# LCD_KEYb_final_rev02.net
KiCad netlist of a schematic drawn in EAGLE
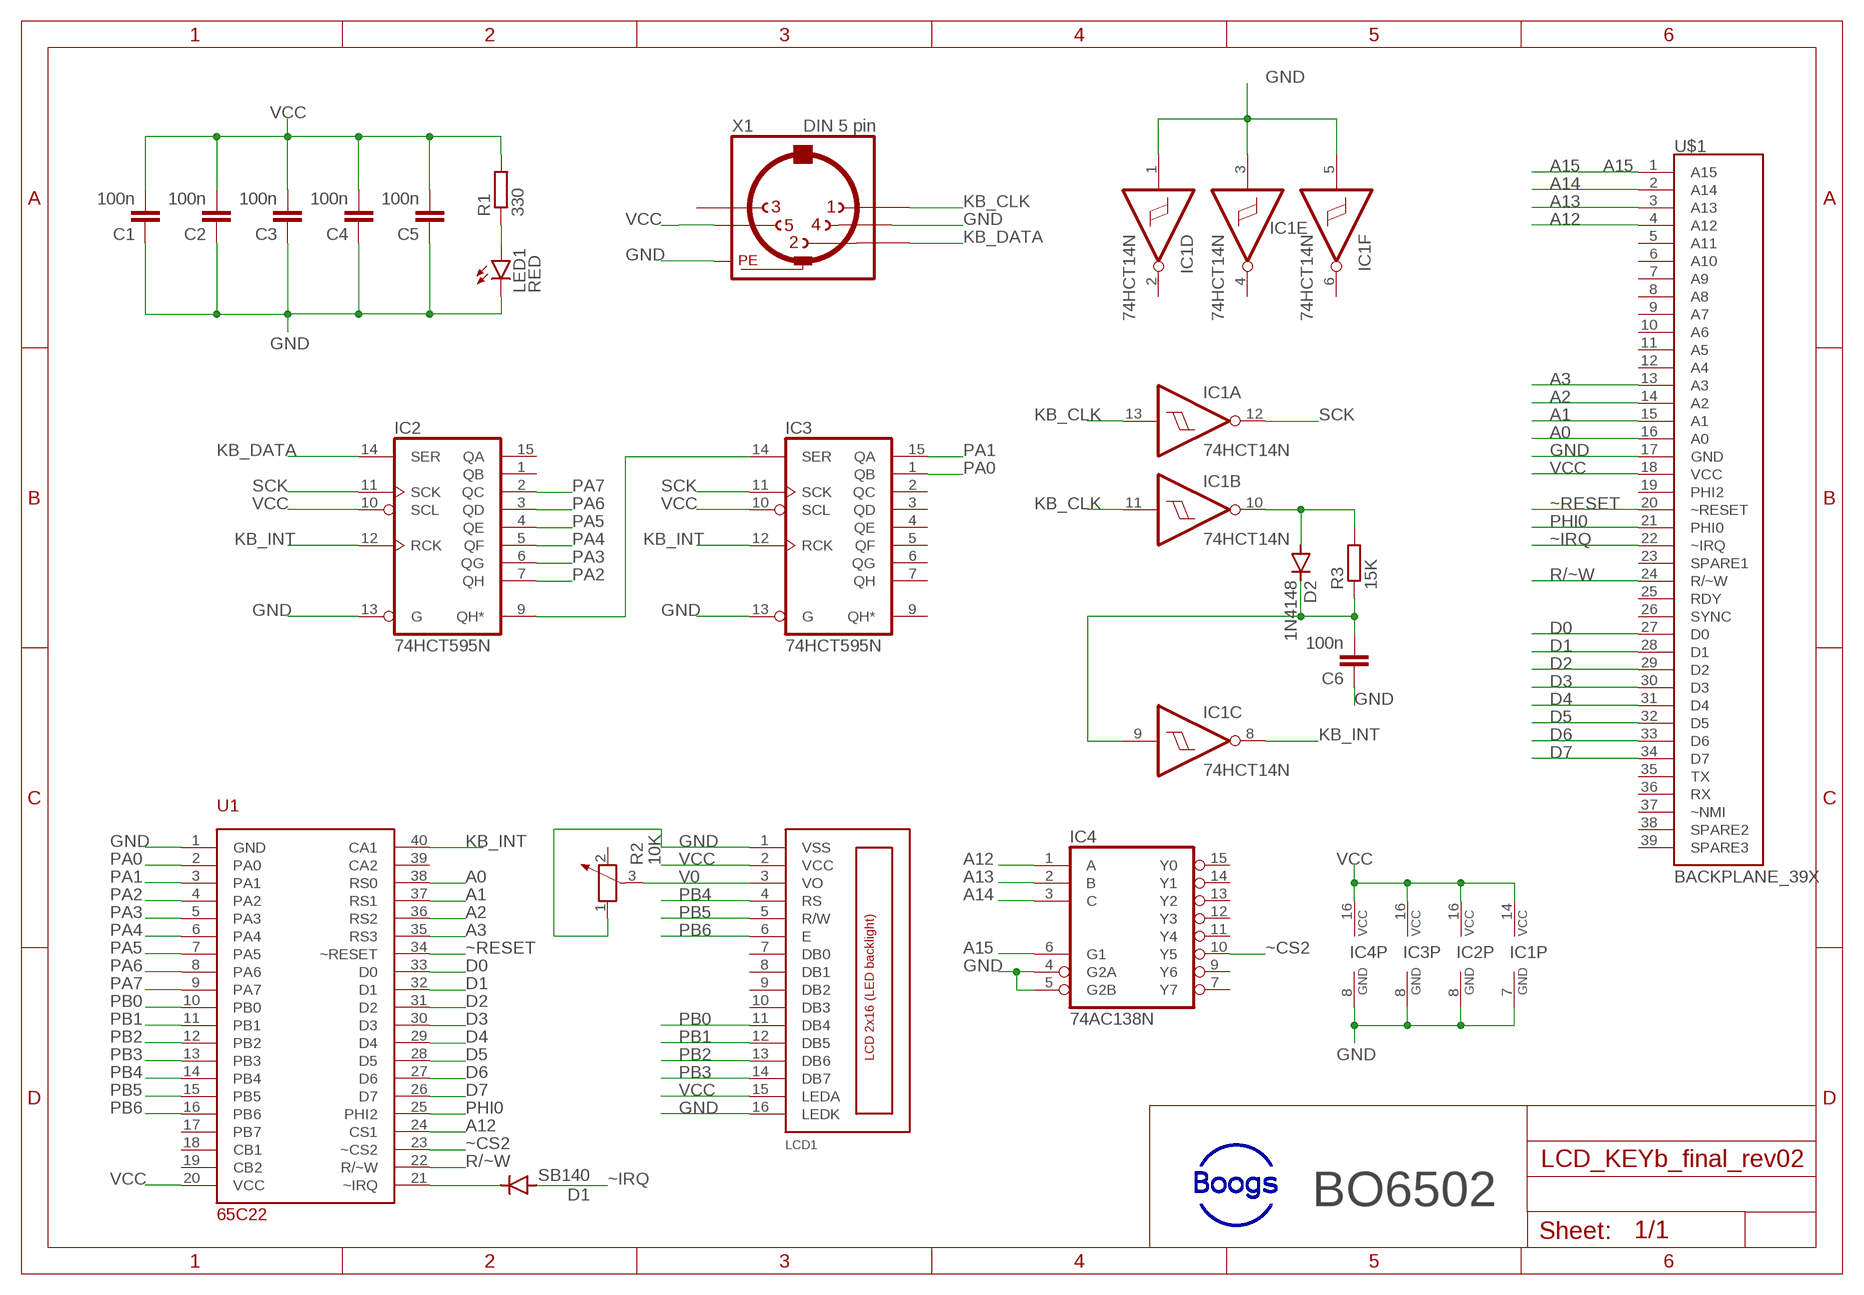
[diagram p0: schematic, sheet 1]

(export (version "E")
  (design (tool "Eeschema 10.0.6"))
  (components
    (comp (ref "C1")
      (value "100n")
      (footprint "eagle-import:C025-025X050")
      (libsource (lib "eagle-import") (part "C-EU025-025X050"))
    )
    (comp (ref "C2")
      (value "100n")
      (footprint "eagle-import:C025-025X050")
      (libsource (lib "eagle-import") (part "C-EU025-025X050"))
    )
    (comp (ref "C3")
      (value "100n")
      (footprint "eagle-import:C025-025X050")
      (libsource (lib "eagle-import") (part "C-EU025-025X050"))
    )
    (comp (ref "C4")
      (value "100n")
      (footprint "eagle-import:C025-025X050")
      (libsource (lib "eagle-import") (part "C-EU025-025X050"))
    )
    (comp (ref "C5")
      (value "100n")
      (footprint "eagle-import:C025-025X050")
      (libsource (lib "eagle-import") (part "C-EU025-025X050"))
    )
    (comp (ref "C6")
      (value "100n")
      (footprint "eagle-import:C025-025X050")
      (libsource (lib "eagle-import") (part "C-EU025-025X050"))
    )
    (comp (ref "D1")
      (value "SB140")
      (footprint "eagle-import:DO41-10")
      (libsource (lib "eagle-import") (part "1N4004"))
    )
    (comp (ref "D2")
      (value "1N4148")
      (footprint "eagle-import:DO35-7")
      (libsource (lib "eagle-import") (part "1N4148DO35-7"))
    )
    (comp (ref "IC1")
      (value "74HCT14N")
      (footprint "eagle-import:DIL14")
      (libsource (lib "eagle-import") (part "7414NHCT"))
    )
    (comp (ref "IC2")
      (value "74HCT595N")
      (footprint "eagle-import:DIL16")
      (libsource (lib "eagle-import") (part "74595NHCT"))
    )
    (comp (ref "IC3")
      (value "74HCT595N")
      (footprint "eagle-import:DIL16")
      (libsource (lib "eagle-import") (part "74595NHCT"))
    )
    (comp (ref "IC4")
      (value "74AC138N")
      (footprint "eagle-import:DIL16")
      (libsource (lib "eagle-import") (part "74138NAC"))
    )
    (comp (ref "LCD1")
      (value "LCD_2X16_SIL")
      (footprint "eagle-import:HY-1602F")
      (libsource (lib "eagle-import") (part "LCD_2X16_SIL"))
    )
    (comp (ref "LED1")
      (value "RED")
      (footprint "eagle-import:LED5MM")
      (libsource (lib "eagle-import") (part "LED5MM"))
    )
    (comp (ref "R1")
      (value "330")
      (footprint "eagle-import:0207_10")
      (libsource (lib "eagle-import") (part "R-EU_0207/10"))
    )
    (comp (ref "R2")
      (value "10K")
      (footprint "eagle-import:PT-10")
      (libsource (lib "eagle-import") (part "POTENTIOMETER_PT-10"))
    )
    (comp (ref "R3")
      (value "15K")
      (footprint "eagle-import:0207_10")
      (libsource (lib "eagle-import") (part "R-EU_0207/10"))
    )
    (comp (ref "U$1")
      (value "BACKPLANE_39X")
      (footprint "eagle-import:BP_39X")
      (fields (field (name "A15") "A15"))
      (libsource (lib "eagle-import") (part "BACKPLANE_39X"))
    )
    (comp (ref "U1")
      (value "65C22")
      (footprint "eagle-import:DIL40")
      (libsource (lib "eagle-import") (part "65C22"))
    )
    (comp (ref "X1")
      (value "DIN 5 pin")
      (footprint "eagle-import:MAB5SH")
      (libsource (lib "eagle-import") (part "MAB5SH"))
    )
  )
  (nets
    (net (code "1") (name "/A0") (class "Default")
      (node (ref "U$1") (pin "16") (pinfunction "A0_16") (pintype "bidirectional"))
      (node (ref "U1") (pin "38") (pinfunction "RS0_38") (pintype "bidirectional"))
    )
    (net (code "2") (name "/A1") (class "Default")
      (node (ref "U$1") (pin "15") (pinfunction "A1_15") (pintype "bidirectional"))
      (node (ref "U1") (pin "37") (pinfunction "RS1_37") (pintype "bidirectional"))
    )
    (net (code "3") (name "/A2") (class "Default")
      (node (ref "U$1") (pin "14") (pinfunction "A2_14") (pintype "bidirectional"))
      (node (ref "U1") (pin "36") (pinfunction "RS2_36") (pintype "bidirectional"))
    )
    (net (code "4") (name "/A3") (class "Default")
      (node (ref "U$1") (pin "13") (pinfunction "A3_13") (pintype "bidirectional"))
      (node (ref "U1") (pin "35") (pinfunction "RS3_35") (pintype "bidirectional"))
    )
    (net (code "5") (name "/A12") (class "Default")
      (node (ref "IC4") (pin "1") (pinfunction "A_1") (pintype "input"))
      (node (ref "U$1") (pin "4") (pinfunction "A12_4") (pintype "bidirectional"))
      (node (ref "U1") (pin "24") (pinfunction "CS1_24") (pintype "bidirectional"))
    )
    (net (code "6") (name "/A13") (class "Default")
      (node (ref "IC4") (pin "2") (pinfunction "B_2") (pintype "input"))
      (node (ref "U$1") (pin "3") (pinfunction "A13_3") (pintype "bidirectional"))
    )
    (net (code "7") (name "/A14") (class "Default")
      (node (ref "IC4") (pin "3") (pinfunction "C_3") (pintype "input"))
      (node (ref "U$1") (pin "2") (pinfunction "A14_2") (pintype "bidirectional"))
    )
    (net (code "8") (name "/A15") (class "Default")
      (node (ref "IC4") (pin "6") (pinfunction "G1_6") (pintype "input"))
      (node (ref "U$1") (pin "1") (pinfunction "A15_1") (pintype "bidirectional"))
    )
    (net (code "9") (name "/D0") (class "Default")
      (node (ref "U$1") (pin "27") (pinfunction "D0_27") (pintype "bidirectional"))
      (node (ref "U1") (pin "33") (pinfunction "D0_33") (pintype "bidirectional"))
    )
    (net (code "10") (name "/D1") (class "Default")
      (node (ref "U$1") (pin "28") (pinfunction "D1_28") (pintype "bidirectional"))
      (node (ref "U1") (pin "32") (pinfunction "D1_32") (pintype "bidirectional"))
    )
    (net (code "11") (name "/D2") (class "Default")
      (node (ref "U$1") (pin "29") (pinfunction "D2_29") (pintype "bidirectional"))
      (node (ref "U1") (pin "31") (pinfunction "D2_31") (pintype "bidirectional"))
    )
    (net (code "12") (name "/D3") (class "Default")
      (node (ref "U$1") (pin "30") (pinfunction "D3_30") (pintype "bidirectional"))
      (node (ref "U1") (pin "30") (pinfunction "D3_30") (pintype "bidirectional"))
    )
    (net (code "13") (name "/D4") (class "Default")
      (node (ref "U$1") (pin "31") (pinfunction "D4_31") (pintype "bidirectional"))
      (node (ref "U1") (pin "29") (pinfunction "D4_29") (pintype "bidirectional"))
    )
    (net (code "14") (name "/D5") (class "Default")
      (node (ref "U$1") (pin "32") (pinfunction "D5_32") (pintype "bidirectional"))
      (node (ref "U1") (pin "28") (pinfunction "D5_28") (pintype "bidirectional"))
    )
    (net (code "15") (name "/D6") (class "Default")
      (node (ref "U$1") (pin "33") (pinfunction "D6_33") (pintype "bidirectional"))
      (node (ref "U1") (pin "27") (pinfunction "D6_27") (pintype "bidirectional"))
    )
    (net (code "16") (name "/D7") (class "Default")
      (node (ref "U$1") (pin "34") (pinfunction "D7_34") (pintype "bidirectional"))
      (node (ref "U1") (pin "26") (pinfunction "D7_26") (pintype "bidirectional"))
    )
    (net (code "17") (name "/GND") (class "Default")
      (node (ref "C1") (pin "1") (pinfunction "1_1") (pintype "passive"))
      (node (ref "C2") (pin "1") (pinfunction "1_1") (pintype "passive"))
      (node (ref "C3") (pin "1") (pinfunction "1_1") (pintype "passive"))
      (node (ref "C4") (pin "1") (pinfunction "1_1") (pintype "passive"))
      (node (ref "C5") (pin "1") (pinfunction "1_1") (pintype "passive"))
      (node (ref "C6") (pin "1") (pinfunction "1_1") (pintype "passive"))
      (node (ref "IC1") (pin "1") (pinfunction "I_1") (pintype "input"))
      (node (ref "IC1") (pin "3") (pinfunction "I_3") (pintype "input"))
      (node (ref "IC1") (pin "5") (pinfunction "I_5") (pintype "input"))
      (node (ref "IC1") (pin "7") (pinfunction "GND_7") (pintype "power_in"))
      (node (ref "IC2") (pin "13") (pinfunction "G_13") (pintype "input"))
      (node (ref "IC2") (pin "8") (pinfunction "GND_8") (pintype "power_in"))
      (node (ref "IC3") (pin "13") (pinfunction "G_13") (pintype "input"))
      (node (ref "IC3") (pin "8") (pinfunction "GND_8") (pintype "power_in"))
      (node (ref "IC4") (pin "4") (pinfunction "G2A_4") (pintype "input"))
      (node (ref "IC4") (pin "5") (pinfunction "G2B_5") (pintype "input"))
      (node (ref "IC4") (pin "8") (pinfunction "GND_8") (pintype "power_in"))
      (node (ref "LCD1") (pin "1") (pinfunction "VSS_1") (pintype "power_in"))
      (node (ref "LCD1") (pin "16") (pinfunction "LEDK_16") (pintype "passive"))
      (node (ref "LED1") (pin "K") (pinfunction "C_K") (pintype "passive"))
      (node (ref "R2") (pin "1") (pinfunction "1_1") (pintype "passive"))
      (node (ref "U$1") (pin "17") (pinfunction "GND_17") (pintype "bidirectional"))
      (node (ref "U1") (pin "1") (pinfunction "GND_1") (pintype "bidirectional"))
      (node (ref "X1") (pin "4") (pinfunction "4_4") (pintype "passive"))
      (node (ref "X1") (pin "PE") (pinfunction "PE_PE") (pintype "power_in"))
      (node (ref "X1") (pin "PE@") (pinfunction "PE_PE@") (pintype "power_in"))
    )
    (net (code "18") (name "/KB_CLK") (class "Default")
      (node (ref "IC1") (pin "11") (pinfunction "I_11") (pintype "input"))
      (node (ref "IC1") (pin "13") (pinfunction "I_13") (pintype "input"))
      (node (ref "X1") (pin "1") (pinfunction "1_1") (pintype "passive"))
    )
    (net (code "19") (name "/KB_DATA") (class "Default")
      (node (ref "IC2") (pin "14") (pinfunction "SER_14") (pintype "input"))
      (node (ref "X1") (pin "2") (pinfunction "2_2") (pintype "passive"))
    )
    (net (code "20") (name "/KB_INT") (class "Default")
      (node (ref "IC1") (pin "8") (pinfunction "O_8") (pintype "output"))
      (node (ref "IC2") (pin "12") (pinfunction "RCK_12") (pintype "input"))
      (node (ref "IC3") (pin "12") (pinfunction "RCK_12") (pintype "input"))
      (node (ref "U1") (pin "40") (pinfunction "CA1_40") (pintype "bidirectional"))
    )
    (net (code "21") (name "/PA0") (class "Default")
      (node (ref "IC3") (pin "1") (pinfunction "QB_1") (pintype "tri_state"))
      (node (ref "U1") (pin "2") (pinfunction "PA0_2") (pintype "bidirectional"))
    )
    (net (code "22") (name "/PA1") (class "Default")
      (node (ref "IC3") (pin "15") (pinfunction "QA_15") (pintype "tri_state"))
      (node (ref "U1") (pin "3") (pinfunction "PA1_3") (pintype "bidirectional"))
    )
    (net (code "23") (name "/PA2") (class "Default")
      (node (ref "IC2") (pin "7") (pinfunction "QH_7") (pintype "tri_state"))
      (node (ref "U1") (pin "4") (pinfunction "PA2_4") (pintype "bidirectional"))
    )
    (net (code "24") (name "/PA3") (class "Default")
      (node (ref "IC2") (pin "6") (pinfunction "QG_6") (pintype "tri_state"))
      (node (ref "U1") (pin "5") (pinfunction "PA3_5") (pintype "bidirectional"))
    )
    (net (code "25") (name "/PA4") (class "Default")
      (node (ref "IC2") (pin "5") (pinfunction "QF_5") (pintype "tri_state"))
      (node (ref "U1") (pin "6") (pinfunction "PA4_6") (pintype "bidirectional"))
    )
    (net (code "26") (name "/PA5") (class "Default")
      (node (ref "IC2") (pin "4") (pinfunction "QE_4") (pintype "tri_state"))
      (node (ref "U1") (pin "7") (pinfunction "PA5_7") (pintype "bidirectional"))
    )
    (net (code "27") (name "/PA6") (class "Default")
      (node (ref "IC2") (pin "3") (pinfunction "QD_3") (pintype "tri_state"))
      (node (ref "U1") (pin "8") (pinfunction "PA6_8") (pintype "bidirectional"))
    )
    (net (code "28") (name "/PA7") (class "Default")
      (node (ref "IC2") (pin "2") (pinfunction "QC_2") (pintype "tri_state"))
      (node (ref "U1") (pin "9") (pinfunction "PA7_9") (pintype "bidirectional"))
    )
    (net (code "29") (name "/PB0") (class "Default")
      (node (ref "LCD1") (pin "11") (pinfunction "DB4_11") (pintype "bidirectional"))
      (node (ref "U1") (pin "10") (pinfunction "PB0_10") (pintype "bidirectional"))
    )
    (net (code "30") (name "/PB1") (class "Default")
      (node (ref "LCD1") (pin "12") (pinfunction "DB5_12") (pintype "bidirectional"))
      (node (ref "U1") (pin "11") (pinfunction "PB1_11") (pintype "bidirectional"))
    )
    (net (code "31") (name "/PB2") (class "Default")
      (node (ref "LCD1") (pin "13") (pinfunction "DB6_13") (pintype "bidirectional"))
      (node (ref "U1") (pin "12") (pinfunction "PB2_12") (pintype "bidirectional"))
    )
    (net (code "32") (name "/PB3") (class "Default")
      (node (ref "LCD1") (pin "14") (pinfunction "DB7_14") (pintype "bidirectional"))
      (node (ref "U1") (pin "13") (pinfunction "PB3_13") (pintype "bidirectional"))
    )
    (net (code "33") (name "/PB4") (class "Default")
      (node (ref "LCD1") (pin "4") (pinfunction "RS_4") (pintype "input"))
      (node (ref "U1") (pin "14") (pinfunction "PB4_14") (pintype "bidirectional"))
    )
    (net (code "34") (name "/PB5") (class "Default")
      (node (ref "LCD1") (pin "5") (pinfunction "R/W_5") (pintype "input"))
      (node (ref "U1") (pin "15") (pinfunction "PB5_15") (pintype "bidirectional"))
    )
    (net (code "35") (name "/PB6") (class "Default")
      (node (ref "LCD1") (pin "6") (pinfunction "E_6") (pintype "input"))
      (node (ref "U1") (pin "16") (pinfunction "PB6_16") (pintype "bidirectional"))
    )
    (net (code "36") (name "/PHI0") (class "Default")
      (node (ref "U$1") (pin "21") (pinfunction "PHI0_21") (pintype "bidirectional"))
      (node (ref "U1") (pin "25") (pinfunction "PHI2_25") (pintype "bidirectional"))
    )
    (net (code "37") (name "/R{slash}~{W}") (class "Default")
      (node (ref "U$1") (pin "24") (pinfunction "R/~{W}_24") (pintype "bidirectional"))
      (node (ref "U1") (pin "22") (pinfunction "R/~{W}_22") (pintype "bidirectional"))
    )
    (net (code "38") (name "/SCK") (class "Default")
      (node (ref "IC1") (pin "12") (pinfunction "O_12") (pintype "output"))
      (node (ref "IC2") (pin "11") (pinfunction "SCK_11") (pintype "input"))
      (node (ref "IC3") (pin "11") (pinfunction "SCK_11") (pintype "input"))
    )
    (net (code "39") (name "/V0") (class "Default")
      (node (ref "LCD1") (pin "3") (pinfunction "VO_3") (pintype "input"))
      (node (ref "R2") (pin "3") (pinfunction "3_3") (pintype "passive"))
    )
    (net (code "40") (name "/VCC") (class "Default")
      (node (ref "C1") (pin "2") (pinfunction "2_2") (pintype "passive"))
      (node (ref "C2") (pin "2") (pinfunction "2_2") (pintype "passive"))
      (node (ref "C3") (pin "2") (pinfunction "2_2") (pintype "passive"))
      (node (ref "C4") (pin "2") (pinfunction "2_2") (pintype "passive"))
      (node (ref "C5") (pin "2") (pinfunction "2_2") (pintype "passive"))
      (node (ref "IC1") (pin "14") (pinfunction "VCC_14") (pintype "power_in"))
      (node (ref "IC2") (pin "10") (pinfunction "SCL_10") (pintype "input"))
      (node (ref "IC2") (pin "16") (pinfunction "VCC_16") (pintype "power_in"))
      (node (ref "IC3") (pin "10") (pinfunction "SCL_10") (pintype "input"))
      (node (ref "IC3") (pin "16") (pinfunction "VCC_16") (pintype "power_in"))
      (node (ref "IC4") (pin "16") (pinfunction "VCC_16") (pintype "power_in"))
      (node (ref "LCD1") (pin "15") (pinfunction "LEDA_15") (pintype "passive"))
      (node (ref "LCD1") (pin "2") (pinfunction "VCC_2") (pintype "power_in"))
      (node (ref "R1") (pin "2") (pinfunction "2_2") (pintype "passive"))
      (node (ref "U$1") (pin "18") (pinfunction "VCC_18") (pintype "bidirectional"))
      (node (ref "U1") (pin "20") (pinfunction "VCC_20") (pintype "bidirectional"))
      (node (ref "X1") (pin "5") (pinfunction "5_5") (pintype "passive"))
    )
    (net (code "41") (name "/~{CS2}") (class "Default")
      (node (ref "IC4") (pin "10") (pinfunction "Y5_10") (pintype "output"))
      (node (ref "U1") (pin "23") (pinfunction "~{CS2}_23") (pintype "bidirectional"))
    )
    (net (code "42") (name "/~{IRQ}") (class "Default")
      (node (ref "D1") (pin "A") (pinfunction "A_A") (pintype "passive"))
      (node (ref "U$1") (pin "22") (pinfunction "~{IRQ}_22") (pintype "bidirectional"))
    )
    (net (code "43") (name "/~{RESET}") (class "Default")
      (node (ref "U$1") (pin "20") (pinfunction "~{RESET}_20") (pintype "bidirectional"))
      (node (ref "U1") (pin "34") (pinfunction "~{RESET}_34") (pintype "bidirectional"))
    )
    (net (code "44") (name "Net-(IC1B-O)") (class "Default")
      (node (ref "D2") (pin "A") (pinfunction "A_A") (pintype "passive"))
      (node (ref "IC1") (pin "10") (pinfunction "O_10") (pintype "output"))
      (node (ref "R3") (pin "2") (pinfunction "2_2") (pintype "passive"))
    )
    (net (code "45") (name "Net-(IC1C-I)") (class "Default")
      (node (ref "C6") (pin "2") (pinfunction "2_2") (pintype "passive"))
      (node (ref "D2") (pin "C") (pinfunction "C_C") (pintype "passive"))
      (node (ref "IC1") (pin "9") (pinfunction "I_9") (pintype "input"))
      (node (ref "R3") (pin "1") (pinfunction "1_1") (pintype "passive"))
    )
    (net (code "46") (name "Net-(IC2A-QH*)") (class "Default")
      (node (ref "IC2") (pin "9") (pinfunction "QH*_9") (pintype "tri_state"))
      (node (ref "IC3") (pin "14") (pinfunction "SER_14") (pintype "input"))
    )
    (net (code "47") (name "Net-(LED1-PadA)") (class "Default")
      (node (ref "LED1") (pin "A") (pinfunction "A_A") (pintype "passive"))
      (node (ref "R1") (pin "1") (pinfunction "1_1") (pintype "passive"))
    )
    (net (code "48") (name "Net-(U1-~{IRQ})") (class "Default")
      (node (ref "D1") (pin "C") (pinfunction "C_C") (pintype "passive"))
      (node (ref "U1") (pin "21") (pinfunction "~{IRQ}_21") (pintype "bidirectional"))
    )
    (net (code "49") (name "unconnected-(IC1D-O-Pad2)") (class "Default")
      (node (ref "IC1") (pin "2") (pinfunction "O_2") (pintype "output"))
    )
    (net (code "50") (name "unconnected-(IC1E-O-Pad4)") (class "Default")
      (node (ref "IC1") (pin "4") (pinfunction "O_4") (pintype "output"))
    )
    (net (code "51") (name "unconnected-(IC1F-O-Pad6)") (class "Default")
      (node (ref "IC1") (pin "6") (pinfunction "O_6") (pintype "output"))
    )
    (net (code "52") (name "unconnected-(IC2A-QA-Pad15)") (class "Default")
      (node (ref "IC2") (pin "15") (pinfunction "QA_15") (pintype "tri_state"))
    )
    (net (code "53") (name "unconnected-(IC2A-QB-Pad1)") (class "Default")
      (node (ref "IC2") (pin "1") (pinfunction "QB_1") (pintype "tri_state"))
    )
    (net (code "54") (name "unconnected-(IC3A-QC-Pad2)") (class "Default")
      (node (ref "IC3") (pin "2") (pinfunction "QC_2") (pintype "tri_state"))
    )
    (net (code "55") (name "unconnected-(IC3A-QD-Pad3)") (class "Default")
      (node (ref "IC3") (pin "3") (pinfunction "QD_3") (pintype "tri_state"))
    )
    (net (code "56") (name "unconnected-(IC3A-QE-Pad4)") (class "Default")
      (node (ref "IC3") (pin "4") (pinfunction "QE_4") (pintype "tri_state"))
    )
    (net (code "57") (name "unconnected-(IC3A-QF-Pad5)") (class "Default")
      (node (ref "IC3") (pin "5") (pinfunction "QF_5") (pintype "tri_state"))
    )
    (net (code "58") (name "unconnected-(IC3A-QG-Pad6)") (class "Default")
      (node (ref "IC3") (pin "6") (pinfunction "QG_6") (pintype "tri_state"))
    )
    (net (code "59") (name "unconnected-(IC3A-QH*-Pad9)") (class "Default")
      (node (ref "IC3") (pin "9") (pinfunction "QH*_9") (pintype "tri_state"))
    )
    (net (code "60") (name "unconnected-(IC3A-QH-Pad7)") (class "Default")
      (node (ref "IC3") (pin "7") (pinfunction "QH_7") (pintype "tri_state"))
    )
    (net (code "61") (name "unconnected-(IC4A-Y0-Pad15)") (class "Default")
      (node (ref "IC4") (pin "15") (pinfunction "Y0_15") (pintype "output"))
    )
    (net (code "62") (name "unconnected-(IC4A-Y1-Pad14)") (class "Default")
      (node (ref "IC4") (pin "14") (pinfunction "Y1_14") (pintype "output"))
    )
    (net (code "63") (name "unconnected-(IC4A-Y2-Pad13)") (class "Default")
      (node (ref "IC4") (pin "13") (pinfunction "Y2_13") (pintype "output"))
    )
    (net (code "64") (name "unconnected-(IC4A-Y3-Pad12)") (class "Default")
      (node (ref "IC4") (pin "12") (pinfunction "Y3_12") (pintype "output"))
    )
    (net (code "65") (name "unconnected-(IC4A-Y4-Pad11)") (class "Default")
      (node (ref "IC4") (pin "11") (pinfunction "Y4_11") (pintype "output"))
    )
    (net (code "66") (name "unconnected-(IC4A-Y6-Pad9)") (class "Default")
      (node (ref "IC4") (pin "9") (pinfunction "Y6_9") (pintype "output"))
    )
    (net (code "67") (name "unconnected-(IC4A-Y7-Pad7)") (class "Default")
      (node (ref "IC4") (pin "7") (pinfunction "Y7_7") (pintype "output"))
    )
    (net (code "68") (name "unconnected-(LCD1-DB0-Pad7)") (class "Default")
      (node (ref "LCD1") (pin "7") (pinfunction "DB0_7") (pintype "bidirectional"))
    )
    (net (code "69") (name "unconnected-(LCD1-DB1-Pad8)") (class "Default")
      (node (ref "LCD1") (pin "8") (pinfunction "DB1_8") (pintype "bidirectional"))
    )
    (net (code "70") (name "unconnected-(LCD1-DB2-Pad9)") (class "Default")
      (node (ref "LCD1") (pin "9") (pinfunction "DB2_9") (pintype "bidirectional"))
    )
    (net (code "71") (name "unconnected-(LCD1-DB3-Pad10)") (class "Default")
      (node (ref "LCD1") (pin "10") (pinfunction "DB3_10") (pintype "bidirectional"))
    )
    (net (code "72") (name "unconnected-(R2-Pad2)") (class "Default")
      (node (ref "R2") (pin "2") (pinfunction "2_2") (pintype "passive"))
    )
    (net (code "73") (name "unconnected-(U$1-A4-Pad12)") (class "Default")
      (node (ref "U$1") (pin "12") (pinfunction "A4_12") (pintype "bidirectional"))
    )
    (net (code "74") (name "unconnected-(U$1-A5-Pad11)") (class "Default")
      (node (ref "U$1") (pin "11") (pinfunction "A5_11") (pintype "bidirectional"))
    )
    (net (code "75") (name "unconnected-(U$1-A6-Pad10)") (class "Default")
      (node (ref "U$1") (pin "10") (pinfunction "A6_10") (pintype "bidirectional"))
    )
    (net (code "76") (name "unconnected-(U$1-A7-Pad9)") (class "Default")
      (node (ref "U$1") (pin "9") (pinfunction "A7_9") (pintype "bidirectional"))
    )
    (net (code "77") (name "unconnected-(U$1-A8-Pad8)") (class "Default")
      (node (ref "U$1") (pin "8") (pinfunction "A8_8") (pintype "bidirectional"))
    )
    (net (code "78") (name "unconnected-(U$1-A9-Pad7)") (class "Default")
      (node (ref "U$1") (pin "7") (pinfunction "A9_7") (pintype "bidirectional"))
    )
    (net (code "79") (name "unconnected-(U$1-A10-Pad6)") (class "Default")
      (node (ref "U$1") (pin "6") (pinfunction "A10_6") (pintype "bidirectional"))
    )
    (net (code "80") (name "unconnected-(U$1-A11-Pad5)") (class "Default")
      (node (ref "U$1") (pin "5") (pinfunction "A11_5") (pintype "bidirectional"))
    )
    (net (code "81") (name "unconnected-(U$1-PHI2-Pad19)") (class "Default")
      (node (ref "U$1") (pin "19") (pinfunction "PHI2_19") (pintype "bidirectional"))
    )
    (net (code "82") (name "unconnected-(U$1-RDY-Pad25)") (class "Default")
      (node (ref "U$1") (pin "25") (pinfunction "RDY_25") (pintype "bidirectional"))
    )
    (net (code "83") (name "unconnected-(U$1-RX-Pad36)") (class "Default")
      (node (ref "U$1") (pin "36") (pinfunction "RX_36") (pintype "bidirectional"))
    )
    (net (code "84") (name "unconnected-(U$1-SPARE1-Pad23)") (class "Default")
      (node (ref "U$1") (pin "23") (pinfunction "SPARE1_23") (pintype "bidirectional"))
    )
    (net (code "85") (name "unconnected-(U$1-SPARE2-Pad38)") (class "Default")
      (node (ref "U$1") (pin "38") (pinfunction "SPARE2_38") (pintype "bidirectional"))
    )
    (net (code "86") (name "unconnected-(U$1-SPARE3-Pad39)") (class "Default")
      (node (ref "U$1") (pin "39") (pinfunction "SPARE3_39") (pintype "bidirectional"))
    )
    (net (code "87") (name "unconnected-(U$1-SYNC-Pad26)") (class "Default")
      (node (ref "U$1") (pin "26") (pinfunction "SYNC_26") (pintype "bidirectional"))
    )
    (net (code "88") (name "unconnected-(U$1-TX-Pad35)") (class "Default")
      (node (ref "U$1") (pin "35") (pinfunction "TX_35") (pintype "bidirectional"))
    )
    (net (code "89") (name "unconnected-(U$1-~{NMI}-Pad37)") (class "Default")
      (node (ref "U$1") (pin "37") (pinfunction "~{NMI}_37") (pintype "bidirectional"))
    )
    (net (code "90") (name "unconnected-(U1-CA2-Pad39)") (class "Default")
      (node (ref "U1") (pin "39") (pinfunction "CA2_39") (pintype "bidirectional"))
    )
    (net (code "91") (name "unconnected-(U1-CB1-Pad18)") (class "Default")
      (node (ref "U1") (pin "18") (pinfunction "CB1_18") (pintype "bidirectional"))
    )
    (net (code "92") (name "unconnected-(U1-CB2-Pad19)") (class "Default")
      (node (ref "U1") (pin "19") (pinfunction "CB2_19") (pintype "bidirectional"))
    )
    (net (code "93") (name "unconnected-(U1-PB7-Pad17)") (class "Default")
      (node (ref "U1") (pin "17") (pinfunction "PB7_17") (pintype "bidirectional"))
    )
    (net (code "94") (name "unconnected-(X1-Pad3)") (class "Default")
      (node (ref "X1") (pin "3") (pinfunction "3_3") (pintype "passive"))
    )
  )
)
